# ALU.net
KiCad netlist of a schematic drawn in Altium Designer
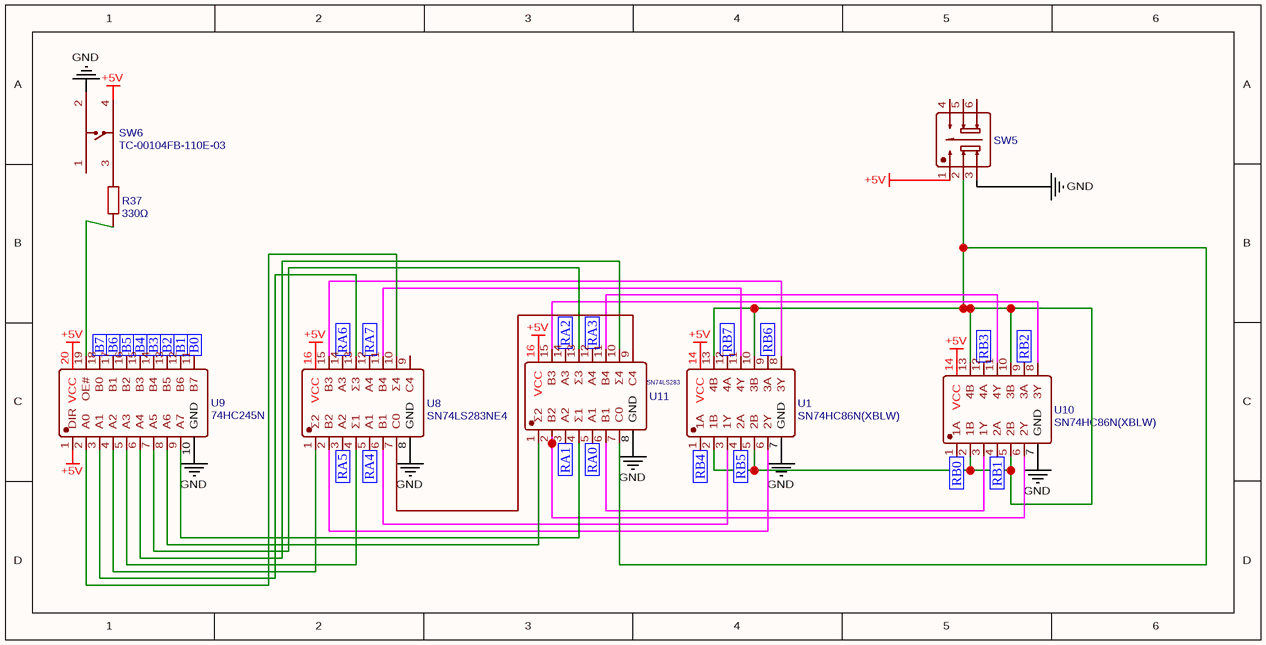
[diagram p0: ALU.schdoc]

(export (version "E")
  (design (tool "Eeschema 10.0.6"))
  (components
    (comp (ref "R37")
      (value "330Ω")
      (fields
        (field (name "MANUFACTURER") "CCO(千志电子)")
        (field (name "MANUFACTURER PART") "MF1/2W-0.1Ω±1% T")
        (field (name "CONTRIBUTOR") "LCSC")
      )
      (libsource (lib "altium-import") (part "root_1_330Ω_"))
    )
    (comp (ref "SW5")
      (value "XKB8585-Z-190")
      (fields (field (name "MANUFACTURER") "XKB Connectivity(中国星坤)") (field (name "CONTRIBUTOR") "LCSC"))
      (libsource (lib "altium-import") (part "root_1_XKB8585-Z-190_"))
    )
    (comp (ref "SW6")
      (value "TC-00104FB-110E-03")
      (fields (field (name "MANUFACTURER") "HOOYA(皓宇电子)") (field (name "CONTRIBUTOR") "lcsc"))
      (libsource (lib "altium-import") (part "root_1_TC-00104FB-110E-03_"))
    )
    (comp (ref "U1")
      (value "SN74HC86N(XBLW)")
      (fields (field (name "MANUFACTURER") "XBLW(芯伯乐)") (field (name "CONTRIBUTOR") "lcsc"))
      (libsource (lib "altium-import") (part "root_1_SN74HC86N(XBLW)_"))
    )
    (comp (ref "U8")
      (value "SN74LS283NE4")
      (fields (field (name "MANUFACTURER") "TI(德州仪器)") (field (name "CONTRIBUTOR") "lcsc"))
      (libsource (lib "altium-import") (part "root_1_SN74LS283NE4_"))
    )
    (comp (ref "U9")
      (value "74HC245N")
      (fields (field (name "MANUFACTURER") "HGSEMI(华冠)") (field (name "CONTRIBUTOR") "LCSC"))
      (libsource (lib "altium-import") (part "root_1_74HC245N_"))
    )
    (comp (ref "U10")
      (value "SN74HC86N(XBLW)")
      (fields (field (name "MANUFACTURER") "XBLW(芯伯乐)") (field (name "CONTRIBUTOR") "lcsc"))
      (libsource (lib "altium-import") (part "root_1_SN74HC86N(XBLW)_"))
    )
    (comp (ref "U11")
      (value "SN74LS283")
      (fields
        (field (name "MANUFACTURER") "TI(德州仪器)")
        (field (name "MANUFACTURER PART") "SN74LS283NE4")
        (field (name "CONTRIBUTOR") "lcsc")
      )
      (libsource (lib "altium-import") (part "root_1_SN74LS283_"))
    )
  )
  (nets
    (net (code "1") (name "+5V") (class "Default")
      (node (ref "SW5") (pin "1") (pinfunction "1_1") (pintype "passive"))
      (node (ref "U1") (pin "14") (pinfunction "VCC_14") (pintype "passive"))
      (node (ref "U10") (pin "14") (pinfunction "VCC_14") (pintype "passive"))
      (node (ref "U11") (pin "16") (pinfunction "VCC_16") (pintype "passive"))
      (node (ref "U8") (pin "16") (pinfunction "VCC_16") (pintype "passive"))
      (node (ref "U9") (pin "1") (pinfunction "DIR_1") (pintype "passive"))
      (node (ref "U9") (pin "20") (pinfunction "VCC_20") (pintype "passive"))
    )
    (net (code "2") (name "/B0") (class "Default")
      (node (ref "U9") (pin "11") (pinfunction "B7_11") (pintype "passive"))
    )
    (net (code "3") (name "/B1") (class "Default")
      (node (ref "U9") (pin "12") (pinfunction "B6_12") (pintype "passive"))
    )
    (net (code "4") (name "/B2") (class "Default")
      (node (ref "U9") (pin "13") (pinfunction "B5_13") (pintype "passive"))
    )
    (net (code "5") (name "/B3") (class "Default")
      (node (ref "U9") (pin "14") (pinfunction "B4_14") (pintype "passive"))
    )
    (net (code "6") (name "/B4") (class "Default")
      (node (ref "U9") (pin "15") (pinfunction "B3_15") (pintype "passive"))
    )
    (net (code "7") (name "/B5") (class "Default")
      (node (ref "U9") (pin "16") (pinfunction "B2_16") (pintype "passive"))
    )
    (net (code "8") (name "/B6") (class "Default")
      (node (ref "U9") (pin "17") (pinfunction "B1_17") (pintype "passive"))
    )
    (net (code "9") (name "/B7") (class "Default")
      (node (ref "U9") (pin "18") (pinfunction "B0_18") (pintype "passive"))
    )
    (net (code "10") (name "/RA0") (class "Default")
      (node (ref "U11") (pin "5") (pinfunction "A1_5") (pintype "passive"))
    )
    (net (code "11") (name "/RA1") (class "Default")
      (node (ref "U11") (pin "3") (pinfunction "A2_3") (pintype "passive"))
    )
    (net (code "12") (name "/RA2") (class "Default")
      (node (ref "U11") (pin "14") (pinfunction "A3_14") (pintype "passive"))
    )
    (net (code "13") (name "/RA3") (class "Default")
      (node (ref "U11") (pin "12") (pinfunction "A4_12") (pintype "passive"))
    )
    (net (code "14") (name "/RA4") (class "Default")
      (node (ref "U8") (pin "5") (pinfunction "A1_5") (pintype "passive"))
    )
    (net (code "15") (name "/RA5") (class "Default")
      (node (ref "U8") (pin "3") (pinfunction "A2_3") (pintype "passive"))
    )
    (net (code "16") (name "/RA6") (class "Default")
      (node (ref "U8") (pin "14") (pinfunction "A3_14") (pintype "passive"))
    )
    (net (code "17") (name "/RA7") (class "Default")
      (node (ref "U8") (pin "12") (pinfunction "A4_12") (pintype "passive"))
    )
    (net (code "18") (name "/RB0") (class "Default")
      (node (ref "U10") (pin "1") (pinfunction "1A_1") (pintype "passive"))
    )
    (net (code "19") (name "/RB1") (class "Default")
      (node (ref "U10") (pin "4") (pinfunction "2A_4") (pintype "passive"))
    )
    (net (code "20") (name "/RB2") (class "Default")
      (node (ref "U10") (pin "9") (pinfunction "3A_9") (pintype "passive"))
    )
    (net (code "21") (name "/RB3") (class "Default")
      (node (ref "U10") (pin "12") (pinfunction "4A_12") (pintype "passive"))
    )
    (net (code "22") (name "/RB4") (class "Default")
      (node (ref "U1") (pin "1") (pinfunction "1A_1") (pintype "passive"))
    )
    (net (code "23") (name "/RB5") (class "Default")
      (node (ref "U1") (pin "4") (pinfunction "2A_4") (pintype "passive"))
    )
    (net (code "24") (name "/RB6") (class "Default")
      (node (ref "U1") (pin "9") (pinfunction "3A_9") (pintype "passive"))
    )
    (net (code "25") (name "/RB7") (class "Default")
      (node (ref "U1") (pin "12") (pinfunction "4A_12") (pintype "passive"))
    )
    (net (code "26") (name "GND") (class "Default")
      (node (ref "SW5") (pin "3") (pinfunction "3_3") (pintype "passive"))
      (node (ref "SW6") (pin "2") (pinfunction "2_2") (pintype "passive"))
      (node (ref "U1") (pin "7") (pinfunction "GND_7") (pintype "passive"))
      (node (ref "U10") (pin "7") (pinfunction "GND_7") (pintype "passive"))
      (node (ref "U11") (pin "8") (pinfunction "GND_8") (pintype "passive"))
      (node (ref "U8") (pin "8") (pinfunction "GND_8") (pintype "passive"))
      (node (ref "U9") (pin "10") (pinfunction "GND_10") (pintype "passive"))
    )
    (net (code "27") (name "Net-(R37-Pad2)") (class "Default")
      (node (ref "R37") (pin "2") (pinfunction "2_2") (pintype "passive"))
      (node (ref "SW6") (pin "3") (pinfunction "3_3") (pintype "passive"))
    )
    (net (code "28") (name "Net-(U1-1B)") (class "Default")
      (node (ref "SW5") (pin "2") (pinfunction "2_2") (pintype "passive"))
      (node (ref "U1") (pin "10") (pinfunction "3B_10") (pintype "passive"))
      (node (ref "U1") (pin "13") (pinfunction "4B_13") (pintype "passive"))
      (node (ref "U1") (pin "2") (pinfunction "1B_2") (pintype "passive"))
      (node (ref "U1") (pin "5") (pinfunction "2B_5") (pintype "passive"))
      (node (ref "U10") (pin "10") (pinfunction "3B_10") (pintype "passive"))
      (node (ref "U10") (pin "13") (pinfunction "4B_13") (pintype "passive"))
      (node (ref "U10") (pin "2") (pinfunction "1B_2") (pintype "passive"))
      (node (ref "U10") (pin "5") (pinfunction "2B_5") (pintype "passive"))
      (node (ref "U11") (pin "7") (pinfunction "C0_7") (pintype "passive"))
    )
    (net (code "29") (name "Net-(U1-1Y)") (class "Default")
      (node (ref "U1") (pin "3") (pinfunction "1Y_3") (pintype "passive"))
      (node (ref "U8") (pin "6") (pinfunction "B1_6") (pintype "passive"))
    )
    (net (code "30") (name "Net-(U1-2Y)") (class "Default")
      (node (ref "U1") (pin "6") (pinfunction "2Y_6") (pintype "passive"))
      (node (ref "U8") (pin "2") (pinfunction "B2_2") (pintype "passive"))
    )
    (net (code "31") (name "Net-(U1-3Y)") (class "Default")
      (node (ref "U1") (pin "8") (pinfunction "3Y_8") (pintype "passive"))
      (node (ref "U8") (pin "15") (pinfunction "B3_15") (pintype "passive"))
    )
    (net (code "32") (name "Net-(U1-4Y)") (class "Default")
      (node (ref "U1") (pin "11") (pinfunction "4Y_11") (pintype "passive"))
      (node (ref "U8") (pin "11") (pinfunction "B4_11") (pintype "passive"))
    )
    (net (code "33") (name "Net-(U8-Σ1)") (class "Default")
      (node (ref "U8") (pin "4") (pinfunction "Σ1_4") (pintype "passive"))
      (node (ref "U9") (pin "5") (pinfunction "A3_5") (pintype "passive"))
    )
    (net (code "34") (name "Net-(U8-Σ2)") (class "Default")
      (node (ref "U8") (pin "1") (pinfunction "Σ2_1") (pintype "passive"))
      (node (ref "U9") (pin "4") (pinfunction "A2_4") (pintype "passive"))
    )
    (net (code "35") (name "Net-(U8-Σ3)") (class "Default")
      (node (ref "U8") (pin "13") (pinfunction "Σ3_13") (pintype "passive"))
      (node (ref "U9") (pin "3") (pinfunction "A1_3") (pintype "passive"))
    )
    (net (code "36") (name "Net-(U8-Σ4)") (class "Default")
      (node (ref "U8") (pin "10") (pinfunction "Σ4_10") (pintype "passive"))
      (node (ref "U9") (pin "2") (pinfunction "A0_2") (pintype "passive"))
    )
    (net (code "37") (name "Net-(U9-OE#)") (class "Default")
      (node (ref "R37") (pin "1") (pinfunction "1_1") (pintype "passive"))
      (node (ref "U9") (pin "19") (pinfunction "OE#_19") (pintype "passive"))
    )
    (net (code "38") (name "Net-(U10-1Y)") (class "Default")
      (node (ref "U10") (pin "3") (pinfunction "1Y_3") (pintype "passive"))
      (node (ref "U11") (pin "6") (pinfunction "B1_6") (pintype "passive"))
    )
    (net (code "39") (name "Net-(U10-2Y)") (class "Default")
      (node (ref "U10") (pin "6") (pinfunction "2Y_6") (pintype "passive"))
      (node (ref "U11") (pin "2") (pinfunction "B2_2") (pintype "passive"))
    )
    (net (code "40") (name "Net-(U10-3Y)") (class "Default")
      (node (ref "U10") (pin "8") (pinfunction "3Y_8") (pintype "passive"))
      (node (ref "U11") (pin "15") (pinfunction "B3_15") (pintype "passive"))
    )
    (net (code "41") (name "Net-(U10-4Y)") (class "Default")
      (node (ref "U10") (pin "11") (pinfunction "4Y_11") (pintype "passive"))
      (node (ref "U11") (pin "11") (pinfunction "B4_11") (pintype "passive"))
    )
    (net (code "42") (name "Net-(U11-C4)") (class "Default")
      (node (ref "U11") (pin "9") (pinfunction "C4_9") (pintype "passive"))
      (node (ref "U8") (pin "7") (pinfunction "C0_7") (pintype "passive"))
    )
    (net (code "43") (name "Net-(U11-Σ1)") (class "Default")
      (node (ref "U11") (pin "4") (pinfunction "Σ1_4") (pintype "passive"))
      (node (ref "U9") (pin "9") (pinfunction "A7_9") (pintype "passive"))
    )
    (net (code "44") (name "Net-(U11-Σ2)") (class "Default")
      (node (ref "U11") (pin "1") (pinfunction "Σ2_1") (pintype "passive"))
      (node (ref "U9") (pin "8") (pinfunction "A6_8") (pintype "passive"))
    )
    (net (code "45") (name "Net-(U11-Σ3)") (class "Default")
      (node (ref "U11") (pin "13") (pinfunction "Σ3_13") (pintype "passive"))
      (node (ref "U9") (pin "7") (pinfunction "A5_7") (pintype "passive"))
    )
    (net (code "46") (name "Net-(U11-Σ4)") (class "Default")
      (node (ref "U11") (pin "10") (pinfunction "Σ4_10") (pintype "passive"))
      (node (ref "U9") (pin "6") (pinfunction "A4_6") (pintype "passive"))
    )
    (net (code "47") (name "unconnected-(SW5-Pad4)") (class "Default")
      (node (ref "SW5") (pin "4") (pinfunction "4_4") (pintype "passive"))
    )
    (net (code "48") (name "unconnected-(SW5-Pad5)") (class "Default")
      (node (ref "SW5") (pin "5") (pinfunction "5_5") (pintype "passive"))
    )
    (net (code "49") (name "unconnected-(SW5-Pad6)") (class "Default")
      (node (ref "SW5") (pin "6") (pinfunction "6_6") (pintype "passive"))
    )
    (net (code "50") (name "unconnected-(SW6-Pad1)") (class "Default")
      (node (ref "SW6") (pin "1") (pinfunction "1_1") (pintype "passive"))
    )
    (net (code "51") (name "unconnected-(SW6-Pad4)") (class "Default")
      (node (ref "SW6") (pin "4") (pinfunction "4_4") (pintype "passive"))
    )
    (net (code "52") (name "unconnected-(U8-C4-Pad9)") (class "Default")
      (node (ref "U8") (pin "9") (pinfunction "C4_9") (pintype "passive"))
    )
  )
)
